# Driver_Morpheu_v4_0_SENSOR_CORRENTE.net
KiCad netlist of a schematic drawn in Altium Designer
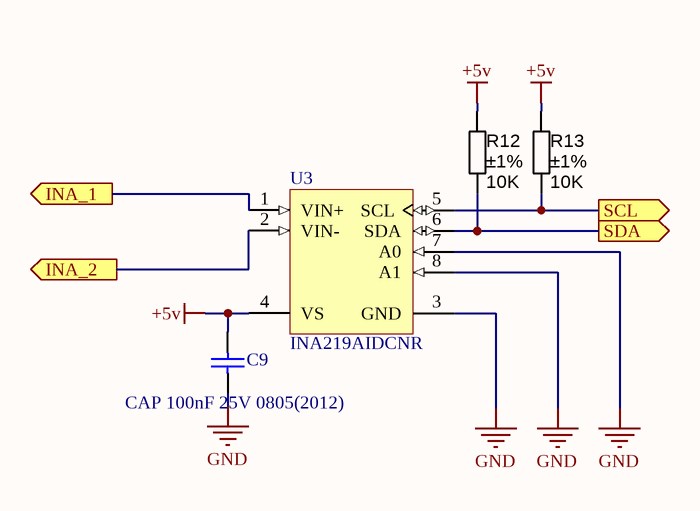
[diagram p0: Driver Morpheu v4.0 SENSOR CORRENTE.SchDoc]

(export (version "E")
  (design (tool "Eeschema 10.0.6"))
  (components
    (comp (ref "C9")
      (value "CAP 100nF 25V 0805(2012)")
      (footprint "CAPC0805(2012)145_M")
      (description "CAP 100nF 25V ±5% 0805 (2012 Metric) Thickness 1.45mm SMD")
      (fields (field (name "TOLERANCE") "Â±5%"))
      (libsource (lib "Altium Content Vault") (part "CAP"))
    )
    (comp (ref "R12")
      (value "10K")
      (footprint "RESC1608X55N")
      (description "Resistor SMD chip 10k Ohm 0.1W 1% 0603")
      (fields (field (name "TOLERANCE") "±1%") (field (name "Comment") "Thick Film"))
      (libsource (lib "PBL - Resistors") (part "RES_10K_0603_1%"))
    )
    (comp (ref "R13")
      (value "10K")
      (footprint "RESC1608X55N")
      (description "Resistor SMD chip 10k Ohm 0.1W 1% 0603")
      (fields (field (name "TOLERANCE") "±1%") (field (name "Comment") "Thick Film"))
      (libsource (lib "PBL - Resistors") (part "RES_10K_0603_1%"))
    )
    (comp (ref "U3")
      (value "INA219AIDCNR")
      (footprint "DCN0008A_M")
      (fields (field (name "MANUFACTURER") "Texas Instruments"))
      (libsource (lib "Altium Content Vault") (part "TI-INA219DCN8"))
    )
  )
  (nets
    (net (code "1") (name "+5v") (class "Default")
      (node (ref "C9") (pin "2") (pinfunction "2_2") (pintype "passive"))
      (node (ref "R12") (pin "1") (pinfunction "1_1") (pintype "passive"))
      (node (ref "R13") (pin "1") (pinfunction "1_1") (pintype "passive"))
      (node (ref "U3") (pin "4") (pinfunction "VS_4") (pintype "power_in"))
    )
    (net (code "2") (name "/INA_1") (class "Default")
      (node (ref "U3") (pin "1") (pinfunction "VIN+_1") (pintype "input"))
    )
    (net (code "3") (name "/INA_2") (class "Default")
      (node (ref "U3") (pin "2") (pinfunction "VIN-_2") (pintype "input"))
    )
    (net (code "4") (name "/SCL") (class "Default")
      (node (ref "R13") (pin "2") (pinfunction "2_2") (pintype "passive"))
      (node (ref "U3") (pin "5") (pinfunction "SCL_5") (pintype "bidirectional"))
    )
    (net (code "5") (name "/SDA") (class "Default")
      (node (ref "R12") (pin "2") (pinfunction "2_2") (pintype "passive"))
      (node (ref "U3") (pin "6") (pinfunction "SDA_6") (pintype "bidirectional"))
    )
    (net (code "6") (name "GND") (class "Default")
      (node (ref "C9") (pin "1") (pinfunction "1_1") (pintype "passive"))
      (node (ref "U3") (pin "3") (pinfunction "GND_3") (pintype "power_in"))
      (node (ref "U3") (pin "7") (pinfunction "A0_7") (pintype "input"))
      (node (ref "U3") (pin "8") (pinfunction "A1_8") (pintype "input"))
    )
  )
)
